# JLinkWiFi.net
KiCad netlist of a schematic drawn in EasyEDA Pro
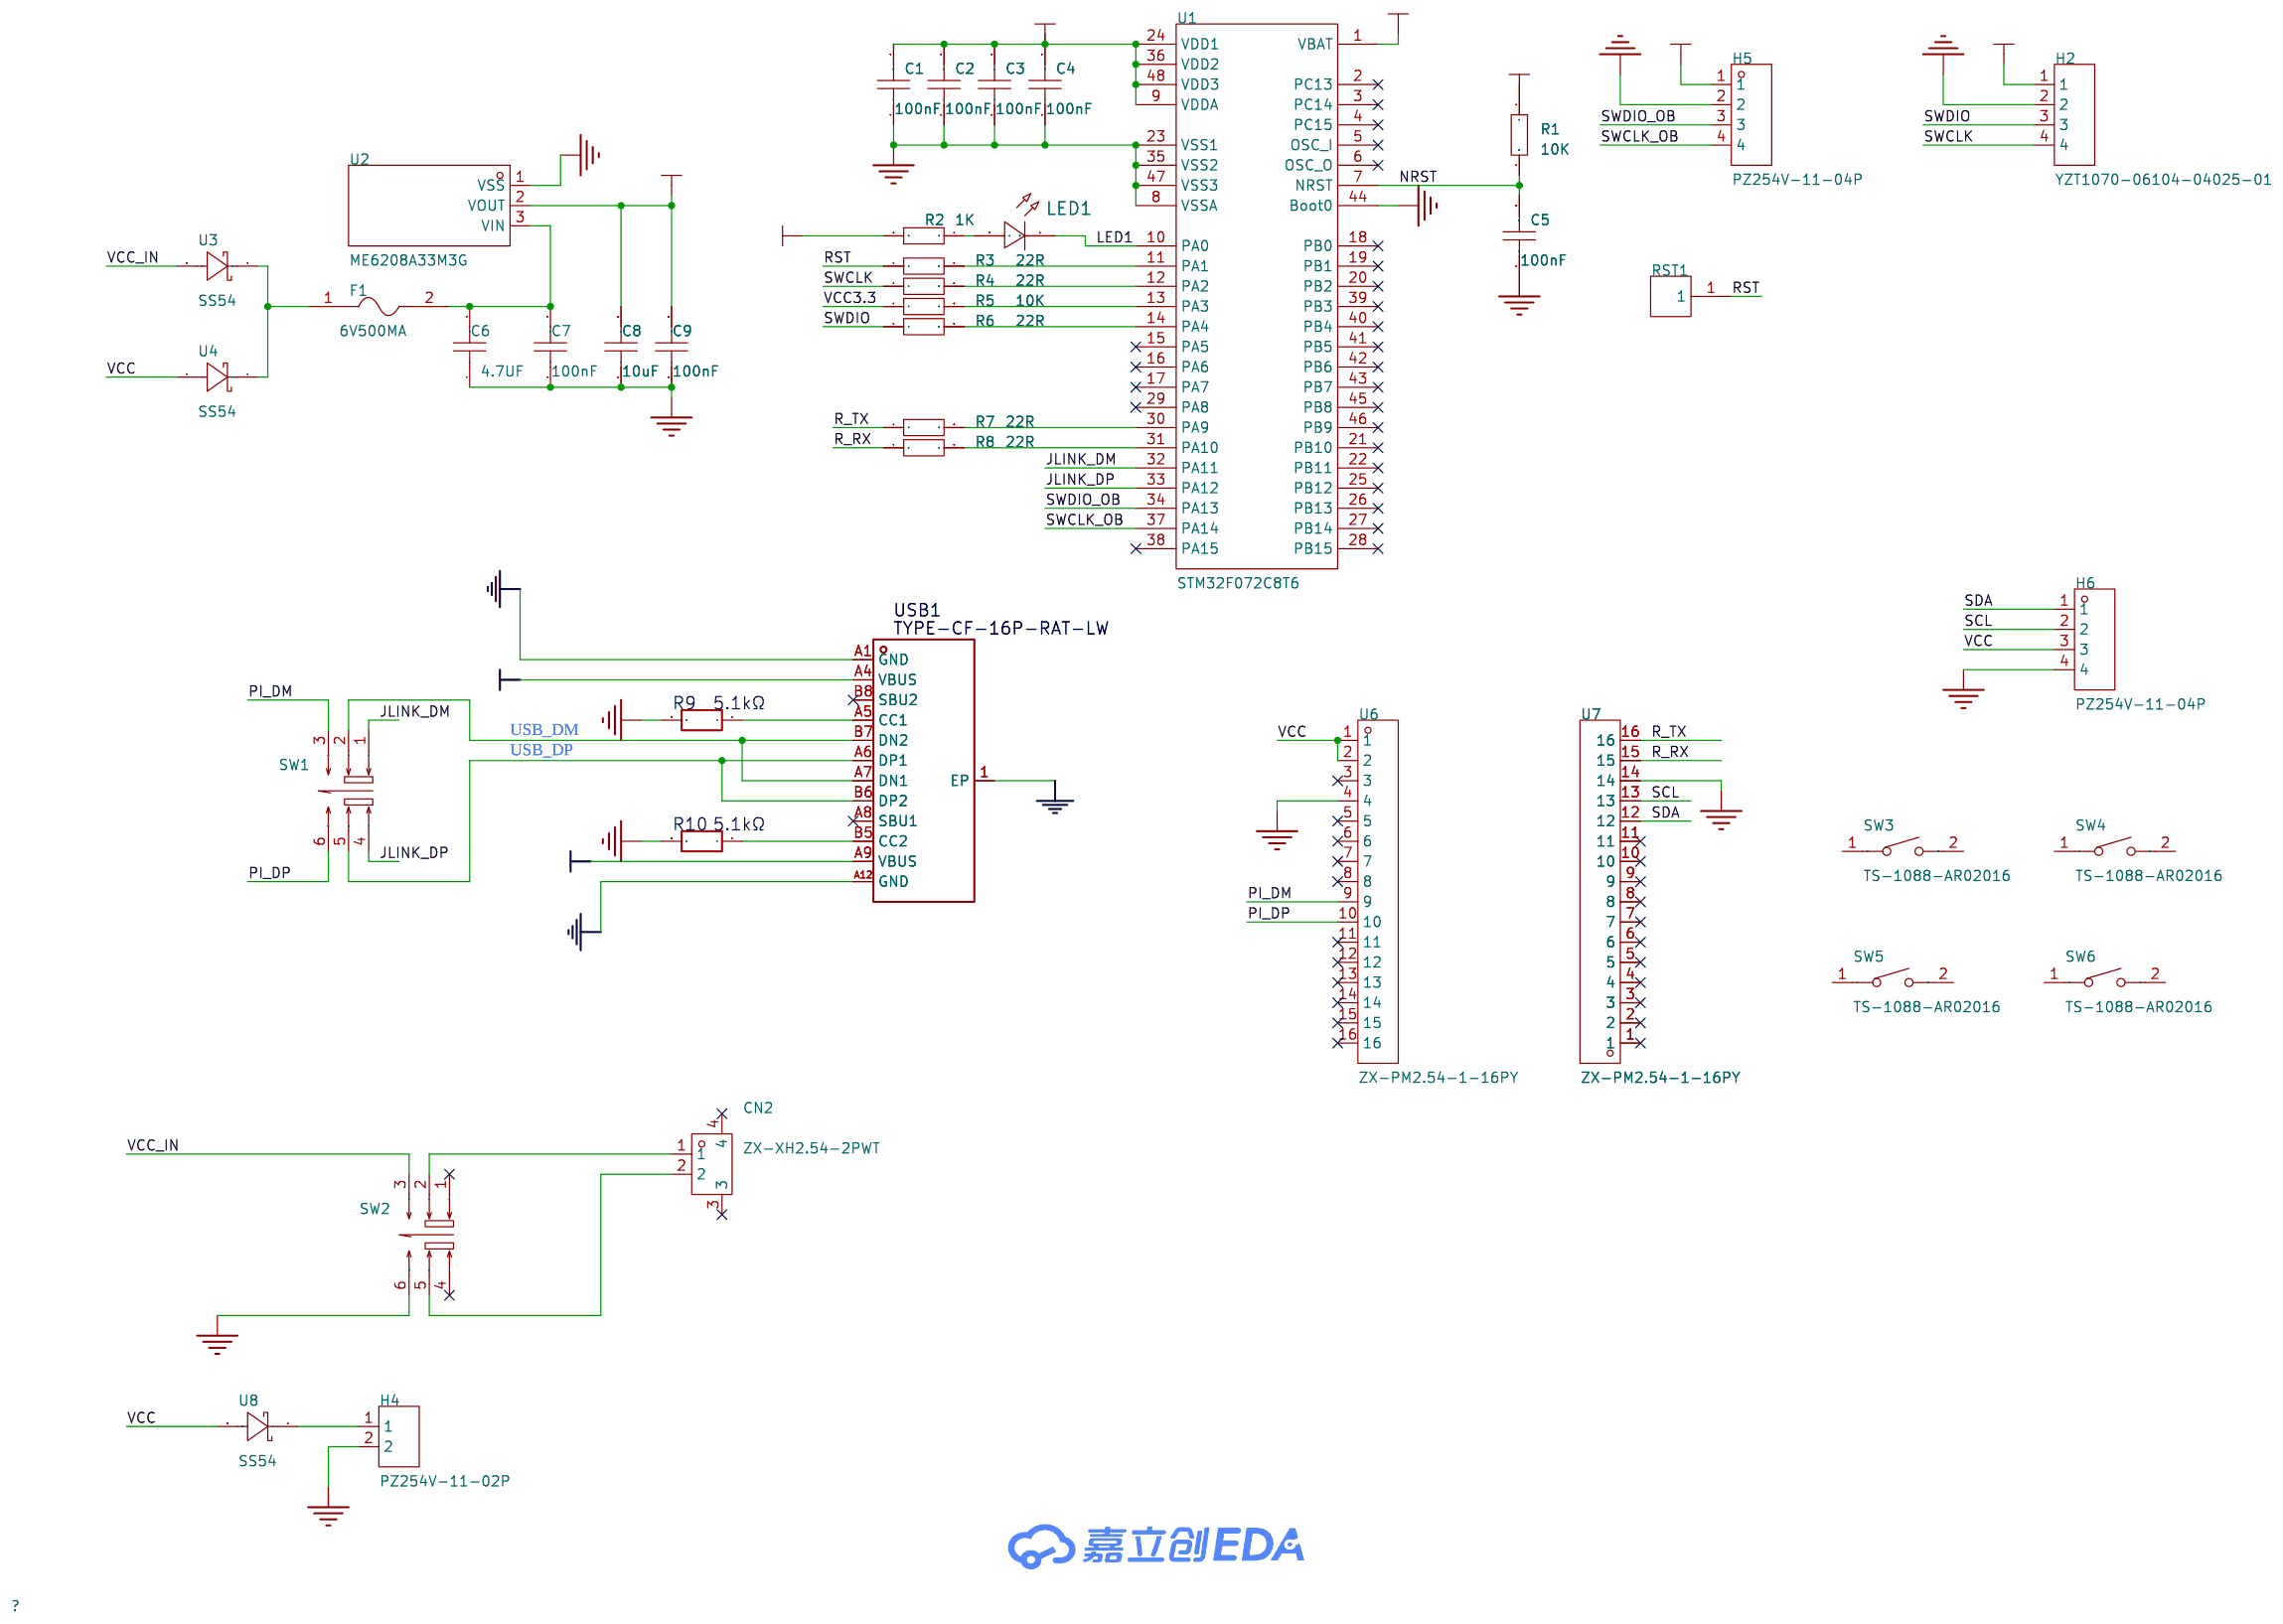
[diagram p0: schematic sheet]

(export (version "E")
  (design (tool "Eeschema 10.0.6"))
  (components
    (comp (ref "C1")
      (value "100nF")
      (footprint "easyedapro:C0603")
      (libsource (lib "easyedapro") (part "CapAcitance"))
    )
    (comp (ref "C2")
      (value "100nF")
      (footprint "easyedapro:C0603")
      (libsource (lib "easyedapro") (part "CapAcitance"))
    )
    (comp (ref "C3")
      (value "100nF")
      (footprint "easyedapro:C0603")
      (libsource (lib "easyedapro") (part "CapAcitance"))
    )
    (comp (ref "C4")
      (value "100nF")
      (footprint "easyedapro:C0603")
      (libsource (lib "easyedapro") (part "CapAcitance"))
    )
    (comp (ref "C5")
      (value "100nF")
      (footprint "easyedapro:C0603")
      (libsource (lib "easyedapro") (part "CapAcitance"))
    )
    (comp (ref "C6")
      (value "4.7UF")
      (footprint "easyedapro:C0603")
      (libsource (lib "easyedapro") (part "CapAcitance"))
    )
    (comp (ref "C7")
      (value "100nF")
      (footprint "easyedapro:C0603")
      (libsource (lib "easyedapro") (part "CapAcitance"))
    )
    (comp (ref "C8")
      (value "10uF")
      (footprint "easyedapro:C0603")
      (libsource (lib "easyedapro") (part "CapAcitance"))
    )
    (comp (ref "C9")
      (value "100nF")
      (footprint "easyedapro:C0603")
      (libsource (lib "easyedapro") (part "CapAcitance"))
    )
    (comp (ref "CN2")
      (value "ZX-XH2.54-2PWT")
      (footprint "easyedapro:CONN-SMD_2P-P2.54_MEGASTAR_ZX-XH2.54-2PWT")
      (fields (field (name "Manufacturer") "Megastar(兆星)"))
      (libsource (lib "easyedapro") (part "ZX-XH2.54-2PWT"))
    )
    (comp (ref "F1")
      (value "6V500MA")
      (footprint "easyedapro:F0805")
      (description "最大电压:24V;最大电流:100A;保持电流:100mA;跳闸电流:300mA;")
      (fields (field (name "Manufacturer") "台湾陆海"))
      (libsource (lib "easyedapro") (part "SMD0805-010-24V"))
    )
    (comp (ref "H2")
      (value "YZT1070-06104-04025-01")
      (footprint "easyedapro:HDR-TH_4P-P2.54-H-M-W6.0")
      (description "间距:2.54mm;总PIN位数:4P;")
      (fields (field (name "Manufacturer") "Xinyangze(鑫扬泽)"))
      (libsource (lib "easyedapro") (part "YZT1070-06104-04025-01"))
    )
    (comp (ref "H4")
      (value "PZ254V-11-02P")
      (footprint "easyedapro:HDR-TH_2P-P2.54-V-M")
      (fields (field (name "Manufacturer") "XFCN(兴飞)"))
      (libsource (lib "easyedapro") (part "PZ254V-11-02P"))
    )
    (comp (ref "H5")
      (value "PZ254V-11-04P")
      (footprint "easyedapro:HDR-TH_4P-P2.54-V-M")
      (fields (field (name "Manufacturer") "XFCN(兴飞)"))
      (libsource (lib "easyedapro") (part "PZ254V-11-04P_C2691448"))
    )
    (comp (ref "H6")
      (value "PZ254V-11-04P")
      (footprint "easyedapro:HDR-TH_4P-P2.54-V-M")
      (fields (field (name "Manufacturer") "XFCN(兴飞)"))
      (libsource (lib "easyedapro") (part "PZ254V-11-04P_C2691448"))
    )
    (comp (ref "LED1")
      (value "~")
      (footprint "easyedapro:LED_0603")
      (libsource (lib "easyedapro") (part "LED_R"))
    )
    (comp (ref "R1") (value "10K") (footprint "easyedapro:R0603") (libsource (lib "easyedapro") (part "电阻")))
    (comp (ref "R2") (value "1K") (footprint "easyedapro:R0603") (libsource (lib "easyedapro") (part "电阻")))
    (comp (ref "R3") (value "22R") (footprint "easyedapro:R0603") (libsource (lib "easyedapro") (part "电阻")))
    (comp (ref "R4") (value "22R") (footprint "easyedapro:R0603") (libsource (lib "easyedapro") (part "电阻")))
    (comp (ref "R5") (value "10K") (footprint "easyedapro:R0603") (libsource (lib "easyedapro") (part "电阻")))
    (comp (ref "R6") (value "22R") (footprint "easyedapro:R0603") (libsource (lib "easyedapro") (part "电阻")))
    (comp (ref "R7") (value "22R") (footprint "easyedapro:R0603") (libsource (lib "easyedapro") (part "电阻")))
    (comp (ref "R8") (value "22R") (footprint "easyedapro:R0603") (libsource (lib "easyedapro") (part "电阻")))
    (comp (ref "R9")
      (value "5.1kΩ")
      (footprint "easyedapro:R0603")
      (fields
        (field (name "Manufacturer Part") "MCT0603MG1002BP500")
        (field (name "Manufacturer") "VISHAY(威世)")
      )
      (libsource (lib "easyedapro") (part "10kΩ"))
    )
    (comp (ref "R10")
      (value "5.1kΩ")
      (footprint "easyedapro:R0603")
      (fields
        (field (name "Manufacturer Part") "MCT0603MG1002BP500")
        (field (name "Manufacturer") "VISHAY(威世)")
      )
      (libsource (lib "easyedapro") (part "10kΩ"))
    )
    (comp (ref "RST1")
      (value "~")
      (footprint "easyedapro:PAD_1.5*1.5MM")
      (libsource (lib "easyedapro") (part "测试点1.5x1.5mm"))
    )
    (comp (ref "SW1")
      (value "XKB5858-Z-TP-75")
      (footprint "easyedapro:SW-SMD_6P-L5.8-W5.8-P2.00-LS8.2-BL")
      (description "自锁/无锁:自锁;安装方式:立贴;触点电流:100mA;额定电压:30V;带灯:不带;作用力:1.6N;工作寿命:10万次;")
      (fields (field (name "Manufacturer") "XKB Connection(中国星坤)"))
      (libsource (lib "easyedapro") (part "XKB5858-Z-TP-75"))
    )
    (comp (ref "SW2")
      (value "XKB5858-Z-TP-75")
      (footprint "easyedapro:SW-SMD_6P-L5.8-W5.8-P2.00-LS8.2-BL")
      (description "自锁/无锁:自锁;安装方式:立贴;触点电流:100mA;额定电压:30V;带灯:不带;作用力:1.6N;工作寿命:10万次;")
      (fields (field (name "Manufacturer") "XKB Connection(中国星坤)"))
      (libsource (lib "easyedapro") (part "XKB5858-Z-TP-75"))
    )
    (comp (ref "SW3")
      (value "TS-1088-AR02016")
      (footprint "easyedapro:SW-SMD_L3.9-W3.0-P4.45")
      (fields (field (name "Manufacturer") "XUNPU(讯普)"))
      (libsource (lib "easyedapro") (part "TS-1088-AR02016"))
    )
    (comp (ref "SW4")
      (value "TS-1088-AR02016")
      (footprint "easyedapro:SW-SMD_L3.9-W3.0-P4.45")
      (fields (field (name "Manufacturer") "XUNPU(讯普)"))
      (libsource (lib "easyedapro") (part "TS-1088-AR02016"))
    )
    (comp (ref "SW5")
      (value "TS-1088-AR02016")
      (footprint "easyedapro:SW-SMD_L3.9-W3.0-P4.45")
      (fields (field (name "Manufacturer") "XUNPU(讯普)"))
      (libsource (lib "easyedapro") (part "TS-1088-AR02016"))
    )
    (comp (ref "SW6")
      (value "TS-1088-AR02016")
      (footprint "easyedapro:SW-SMD_L3.9-W3.0-P4.45")
      (fields (field (name "Manufacturer") "XUNPU(讯普)"))
      (libsource (lib "easyedapro") (part "TS-1088-AR02016"))
    )
    (comp (ref "U1")
      (value "STM32F072C8T6")
      (footprint "easyedapro:LQFP-48_L7.0-W7.0-P0.50-LS9.0-BL")
      (fields (field (name "Manufacturer") "ST(意法半导体)"))
      (libsource (lib "easyedapro") (part "STM32F072C8T6"))
    )
    (comp (ref "U2")
      (value "ME6208A33M3G")
      (footprint "easyedapro:SOT-23-3_L2.9-W1.3-P1.90-LS2.4-BR")
      (description "输出类型:固定;输出极性:正;最大输入电压:18V;输出电压:3.3V;输出电流:200mA;电源纹波抑制比(PSRR):-;")
      (fields (field (name "Manufacturer") "MICRONE(南京微盟)"))
      (libsource (lib "easyedapro") (part "ME6208A33M3G"))
    )
    (comp (ref "U3")
      (value "SS54")
      (footprint "easyedapro:SMB_L4.3-W3.6-LS5.4-RD")
      (description "二极管配置:独立式;正向压降(Vf):550mV@5A;直流反向耐压(Vr):40V;整流电流:5A;")
      (fields (field (name "Manufacturer") "HXY MOSFET(华轩阳电子)"))
      (libsource (lib "easyedapro") (part "SS54_C5200096"))
    )
    (comp (ref "U4")
      (value "SS54")
      (footprint "easyedapro:SMB_L4.3-W3.6-LS5.4-RD")
      (description "二极管配置:独立式;正向压降(Vf):550mV@5A;直流反向耐压(Vr):40V;整流电流:5A;")
      (fields (field (name "Manufacturer") "HXY MOSFET(华轩阳电子)"))
      (libsource (lib "easyedapro") (part "SS54_C5200096"))
    )
    (comp (ref "U6")
      (value "ZX-PM2.54-1-16PY")
      (footprint "easyedapro:HDR-TH_16P-P2.54-V-F-1")
      (fields (field (name "Manufacturer") "Megastar(兆星)"))
      (libsource (lib "easyedapro") (part "ZX-PM2.54-1-16PY"))
    )
    (comp (ref "U7")
      (value "ZX-PM2.54-1-16PY")
      (footprint "easyedapro:HDR-TH_16P-P2.54-V-F-1")
      (fields (field (name "Manufacturer") "Megastar(兆星)"))
      (libsource (lib "easyedapro") (part "ZX-PM2.54-1-16PY"))
    )
    (comp (ref "U8")
      (value "SS54")
      (footprint "easyedapro:SMB_L4.3-W3.6-LS5.4-RD")
      (description "二极管配置:独立式;正向压降(Vf):550mV@5A;直流反向耐压(Vr):40V;整流电流:5A;")
      (fields (field (name "Manufacturer") "HXY MOSFET(华轩阳电子)"))
      (libsource (lib "easyedapro") (part "SS54_C5200096"))
    )
    (comp (ref "USB1")
      (value "TYPE-CF-16P-RAT-LW")
      (footprint "easyedapro:TYPE-C-SMD_TYPE-CF-16P-RAT-LW")
      (libsource (lib "easyedapro") (part "TYPE-CF-16P-RAT-LW"))
    )
  )
  (nets
    (net (code "1") (name "/JLINK_DM") (class "Default")
      (node (ref "SW1") (pin "1") (pinfunction "1_1") (pintype "unspecified"))
      (node (ref "U1") (pin "32") (pinfunction "PA11_32") (pintype "input"))
    )
    (net (code "2") (name "/JLINK_DP") (class "Default")
      (node (ref "SW1") (pin "4") (pinfunction "4_4") (pintype "unspecified"))
      (node (ref "U1") (pin "33") (pinfunction "PA12_33") (pintype "input"))
    )
    (net (code "3") (name "/LED1") (class "Default")
      (node (ref "LED1") (pin "1") (pinfunction "C_1") (pintype "input"))
      (node (ref "U1") (pin "10") (pinfunction "PA0_10") (pintype "input"))
    )
    (net (code "4") (name "/NRST") (class "Default")
      (node (ref "C5") (pin "2") (pinfunction "2_2") (pintype "input"))
      (node (ref "R1") (pin "2") (pinfunction "2_2") (pintype "input"))
      (node (ref "U1") (pin "7") (pinfunction "NRST_7") (pintype "input"))
    )
    (net (code "5") (name "/PI_DM") (class "Default")
      (node (ref "SW1") (pin "3") (pinfunction "3_3") (pintype "unspecified"))
      (node (ref "U6") (pin "9") (pinfunction "9_9") (pintype "unspecified"))
    )
    (net (code "6") (name "/PI_DP") (class "Default")
      (node (ref "SW1") (pin "6") (pinfunction "6_6") (pintype "unspecified"))
      (node (ref "U6") (pin "10") (pinfunction "10_10") (pintype "unspecified"))
    )
    (net (code "7") (name "/RST") (class "Default")
      (node (ref "R3") (pin "1") (pinfunction "1_1") (pintype "input"))
      (node (ref "RST1") (pin "1") (pinfunction "1_1") (pintype "input"))
    )
    (net (code "8") (name "/R_RX") (class "Default")
      (node (ref "R8") (pin "1") (pinfunction "1_1") (pintype "input"))
      (node (ref "U7") (pin "15") (pinfunction "15_15") (pintype "unspecified"))
    )
    (net (code "9") (name "/R_TX") (class "Default")
      (node (ref "R7") (pin "1") (pinfunction "1_1") (pintype "input"))
      (node (ref "U7") (pin "16") (pinfunction "16_16") (pintype "unspecified"))
    )
    (net (code "10") (name "/SCL") (class "Default")
      (node (ref "H6") (pin "2") (pinfunction "2_2") (pintype "unspecified"))
      (node (ref "U7") (pin "13") (pinfunction "13_13") (pintype "unspecified"))
    )
    (net (code "11") (name "/SDA") (class "Default")
      (node (ref "H6") (pin "1") (pinfunction "1_1") (pintype "unspecified"))
      (node (ref "U7") (pin "12") (pinfunction "12_12") (pintype "unspecified"))
    )
    (net (code "12") (name "/SWCLK") (class "Default")
      (node (ref "H2") (pin "4") (pinfunction "4_4") (pintype "unspecified"))
      (node (ref "R4") (pin "1") (pinfunction "1_1") (pintype "input"))
    )
    (net (code "13") (name "/SWCLK_OB") (class "Default")
      (node (ref "H5") (pin "4") (pinfunction "4_4") (pintype "unspecified"))
      (node (ref "U1") (pin "37") (pinfunction "PA14_37") (pintype "input"))
    )
    (net (code "14") (name "/SWDIO") (class "Default")
      (node (ref "H2") (pin "3") (pinfunction "3_3") (pintype "unspecified"))
      (node (ref "R6") (pin "1") (pinfunction "1_1") (pintype "input"))
    )
    (net (code "15") (name "/SWDIO_OB") (class "Default")
      (node (ref "H5") (pin "3") (pinfunction "3_3") (pintype "unspecified"))
      (node (ref "U1") (pin "34") (pinfunction "PA13_34") (pintype "input"))
    )
    (net (code "16") (name "/USB_DM") (class "Default")
      (node (ref "SW1") (pin "2") (pinfunction "2_2") (pintype "unspecified"))
      (node (ref "USB1") (pin "A7") (pinfunction "DN1_A7") (pintype "unspecified"))
      (node (ref "USB1") (pin "B7") (pinfunction "DN2_B7") (pintype "unspecified"))
    )
    (net (code "17") (name "/USB_DP") (class "Default")
      (node (ref "SW1") (pin "5") (pinfunction "5_5") (pintype "unspecified"))
      (node (ref "USB1") (pin "A6") (pinfunction "DP1_A6") (pintype "unspecified"))
      (node (ref "USB1") (pin "B6") (pinfunction "DP2_B6") (pintype "unspecified"))
    )
    (net (code "18") (name "/VCC_IN") (class "Default")
      (node (ref "SW2") (pin "3") (pinfunction "3_3") (pintype "unspecified"))
      (node (ref "U3") (pin "2") (pinfunction "2_2") (pintype "unspecified"))
    )
    (net (code "19") (name "GND") (class "Default")
      (node (ref "C1") (pin "1") (pinfunction "1_1") (pintype "input"))
      (node (ref "C2") (pin "1") (pinfunction "1_1") (pintype "input"))
      (node (ref "C3") (pin "1") (pinfunction "1_1") (pintype "input"))
      (node (ref "C4") (pin "1") (pinfunction "1_1") (pintype "input"))
      (node (ref "C5") (pin "1") (pinfunction "1_1") (pintype "input"))
      (node (ref "C6") (pin "1") (pinfunction "1_1") (pintype "input"))
      (node (ref "C7") (pin "1") (pinfunction "1_1") (pintype "input"))
      (node (ref "C8") (pin "1") (pinfunction "1_1") (pintype "input"))
      (node (ref "C9") (pin "1") (pinfunction "1_1") (pintype "input"))
      (node (ref "H2") (pin "2") (pinfunction "2_2") (pintype "unspecified"))
      (node (ref "H4") (pin "2") (pinfunction "2_2") (pintype "unspecified"))
      (node (ref "H5") (pin "2") (pinfunction "2_2") (pintype "unspecified"))
      (node (ref "H6") (pin "4") (pinfunction "4_4") (pintype "unspecified"))
      (node (ref "R10") (pin "2") (pinfunction "2_2") (pintype "unspecified"))
      (node (ref "R9") (pin "2") (pinfunction "2_2") (pintype "unspecified"))
      (node (ref "SW2") (pin "6") (pinfunction "6_6") (pintype "unspecified"))
      (node (ref "U1") (pin "23") (pinfunction "VSS1_23") (pintype "input"))
      (node (ref "U1") (pin "35") (pinfunction "VSS2_35") (pintype "input"))
      (node (ref "U1") (pin "44") (pinfunction "Boot0_44") (pintype "input"))
      (node (ref "U1") (pin "47") (pinfunction "VSS3_47") (pintype "input"))
      (node (ref "U1") (pin "8") (pinfunction "VSSA_8") (pintype "input"))
      (node (ref "U2") (pin "1") (pinfunction "VSS_1") (pintype "input"))
      (node (ref "U6") (pin "4") (pinfunction "4_4") (pintype "unspecified"))
      (node (ref "U7") (pin "14") (pinfunction "14_14") (pintype "unspecified"))
      (node (ref "USB1") (pin "1") (pinfunction "EP_1") (pintype "unspecified"))
      (node (ref "USB1") (pin "A1") (pinfunction "GND_A1") (pintype "unspecified"))
      (node (ref "USB1") (pin "A12") (pinfunction "GND_A12") (pintype "unspecified"))
    )
    (net (code "20") (name "Net-(CN2-Pad1)") (class "Default")
      (node (ref "CN2") (pin "1") (pinfunction "1_1") (pintype "unspecified"))
      (node (ref "SW2") (pin "2") (pinfunction "2_2") (pintype "unspecified"))
    )
    (net (code "21") (name "Net-(CN2-Pad2)") (class "Default")
      (node (ref "CN2") (pin "2") (pinfunction "2_2") (pintype "unspecified"))
      (node (ref "SW2") (pin "5") (pinfunction "5_5") (pintype "unspecified"))
    )
    (net (code "22") (name "Net-(F1-Pad1)") (class "Default")
      (node (ref "F1") (pin "1") (pinfunction "1_1") (pintype "input"))
      (node (ref "U3") (pin "1") (pinfunction "1_1") (pintype "unspecified"))
      (node (ref "U4") (pin "1") (pinfunction "1_1") (pintype "unspecified"))
    )
    (net (code "23") (name "Net-(H4-Pad1)") (class "Default")
      (node (ref "H4") (pin "1") (pinfunction "1_1") (pintype "unspecified"))
      (node (ref "U8") (pin "1") (pinfunction "1_1") (pintype "unspecified"))
    )
    (net (code "24") (name "Net-(LED1-A)") (class "Default")
      (node (ref "LED1") (pin "2") (pinfunction "A_2") (pintype "input"))
      (node (ref "R2") (pin "1") (pinfunction "1_1") (pintype "input"))
    )
    (net (code "25") (name "Net-(U1-PA1)") (class "Default")
      (node (ref "R3") (pin "2") (pinfunction "2_2") (pintype "input"))
      (node (ref "U1") (pin "11") (pinfunction "PA1_11") (pintype "input"))
    )
    (net (code "26") (name "Net-(U1-PA2)") (class "Default")
      (node (ref "R4") (pin "2") (pinfunction "2_2") (pintype "input"))
      (node (ref "U1") (pin "12") (pinfunction "PA2_12") (pintype "input"))
    )
    (net (code "27") (name "Net-(U1-PA3)") (class "Default")
      (node (ref "R5") (pin "2") (pinfunction "2_2") (pintype "input"))
      (node (ref "U1") (pin "13") (pinfunction "PA3_13") (pintype "input"))
    )
    (net (code "28") (name "Net-(U1-PA4)") (class "Default")
      (node (ref "R6") (pin "2") (pinfunction "2_2") (pintype "input"))
      (node (ref "U1") (pin "14") (pinfunction "PA4_14") (pintype "input"))
    )
    (net (code "29") (name "Net-(U1-PA9)") (class "Default")
      (node (ref "R7") (pin "2") (pinfunction "2_2") (pintype "input"))
      (node (ref "U1") (pin "30") (pinfunction "PA9_30") (pintype "input"))
    )
    (net (code "30") (name "Net-(U1-PA10)") (class "Default")
      (node (ref "R8") (pin "2") (pinfunction "2_2") (pintype "input"))
      (node (ref "U1") (pin "31") (pinfunction "PA10_31") (pintype "input"))
    )
    (net (code "31") (name "Net-(U2-VIN)") (class "Default")
      (node (ref "C6") (pin "2") (pinfunction "2_2") (pintype "input"))
      (node (ref "C7") (pin "2") (pinfunction "2_2") (pintype "input"))
      (node (ref "F1") (pin "2") (pinfunction "2_2") (pintype "input"))
      (node (ref "U2") (pin "3") (pinfunction "VIN_3") (pintype "input"))
    )
    (net (code "32") (name "Net-(USB1-CC1)") (class "Default")
      (node (ref "R9") (pin "1") (pinfunction "1_1") (pintype "unspecified"))
      (node (ref "USB1") (pin "A5") (pinfunction "CC1_A5") (pintype "unspecified"))
    )
    (net (code "33") (name "Net-(USB1-CC2)") (class "Default")
      (node (ref "R10") (pin "1") (pinfunction "1_1") (pintype "unspecified"))
      (node (ref "USB1") (pin "B5") (pinfunction "CC2_B5") (pintype "unspecified"))
    )
    (net (code "34") (name "VCC") (class "Default")
      (node (ref "H6") (pin "3") (pinfunction "3_3") (pintype "unspecified"))
      (node (ref "U4") (pin "2") (pinfunction "2_2") (pintype "unspecified"))
      (node (ref "U6") (pin "1") (pinfunction "1_1") (pintype "unspecified"))
      (node (ref "U6") (pin "2") (pinfunction "2_2") (pintype "unspecified"))
      (node (ref "U8") (pin "2") (pinfunction "2_2") (pintype "unspecified"))
      (node (ref "USB1") (pin "A4") (pinfunction "VBUS_A4") (pintype "unspecified"))
      (node (ref "USB1") (pin "A9") (pinfunction "VBUS_A9") (pintype "unspecified"))
    )
    (net (code "35") (name "VCC3.3") (class "Default")
      (node (ref "C1") (pin "2") (pinfunction "2_2") (pintype "input"))
      (node (ref "C2") (pin "2") (pinfunction "2_2") (pintype "input"))
      (node (ref "C3") (pin "2") (pinfunction "2_2") (pintype "input"))
      (node (ref "C4") (pin "2") (pinfunction "2_2") (pintype "input"))
      (node (ref "C8") (pin "2") (pinfunction "2_2") (pintype "input"))
      (node (ref "C9") (pin "2") (pinfunction "2_2") (pintype "input"))
      (node (ref "H2") (pin "1") (pinfunction "1_1") (pintype "unspecified"))
      (node (ref "H5") (pin "1") (pinfunction "1_1") (pintype "unspecified"))
      (node (ref "R1") (pin "1") (pinfunction "1_1") (pintype "input"))
      (node (ref "R2") (pin "2") (pinfunction "2_2") (pintype "input"))
      (node (ref "R5") (pin "1") (pinfunction "1_1") (pintype "input"))
      (node (ref "U1") (pin "1") (pinfunction "VBAT_1") (pintype "input"))
      (node (ref "U1") (pin "24") (pinfunction "VDD1_24") (pintype "input"))
      (node (ref "U1") (pin "36") (pinfunction "VDD2_36") (pintype "input"))
      (node (ref "U1") (pin "48") (pinfunction "VDD3_48") (pintype "input"))
      (node (ref "U1") (pin "9") (pinfunction "VDDA_9") (pintype "input"))
      (node (ref "U2") (pin "2") (pinfunction "VOUT_2") (pintype "input"))
    )
    (net (code "36") (name "unconnected-(CN2-Pad3)") (class "Default")
      (node (ref "CN2") (pin "3") (pinfunction "3_3") (pintype "unspecified+no_connect"))
    )
    (net (code "37") (name "unconnected-(CN2-Pad4)") (class "Default")
      (node (ref "CN2") (pin "4") (pinfunction "4_4") (pintype "unspecified+no_connect"))
    )
    (net (code "38") (name "unconnected-(SW2-Pad1)") (class "Default")
      (node (ref "SW2") (pin "1") (pinfunction "1_1") (pintype "unspecified+no_connect"))
    )
    (net (code "39") (name "unconnected-(SW2-Pad4)") (class "Default")
      (node (ref "SW2") (pin "4") (pinfunction "4_4") (pintype "unspecified+no_connect"))
    )
    (net (code "40") (name "unconnected-(SW3-Pad1)") (class "Default")
      (node (ref "SW3") (pin "1") (pinfunction "1_1") (pintype "unspecified"))
    )
    (net (code "41") (name "unconnected-(SW3-Pad2)") (class "Default")
      (node (ref "SW3") (pin "2") (pinfunction "2_2") (pintype "unspecified"))
    )
    (net (code "42") (name "unconnected-(SW4-Pad1)") (class "Default")
      (node (ref "SW4") (pin "1") (pinfunction "1_1") (pintype "unspecified"))
    )
    (net (code "43") (name "unconnected-(SW4-Pad2)") (class "Default")
      (node (ref "SW4") (pin "2") (pinfunction "2_2") (pintype "unspecified"))
    )
    (net (code "44") (name "unconnected-(SW5-Pad1)") (class "Default")
      (node (ref "SW5") (pin "1") (pinfunction "1_1") (pintype "unspecified"))
    )
    (net (code "45") (name "unconnected-(SW5-Pad2)") (class "Default")
      (node (ref "SW5") (pin "2") (pinfunction "2_2") (pintype "unspecified"))
    )
    (net (code "46") (name "unconnected-(SW6-Pad1)") (class "Default")
      (node (ref "SW6") (pin "1") (pinfunction "1_1") (pintype "unspecified"))
    )
    (net (code "47") (name "unconnected-(SW6-Pad2)") (class "Default")
      (node (ref "SW6") (pin "2") (pinfunction "2_2") (pintype "unspecified"))
    )
    (net (code "48") (name "unconnected-(U1-OSC_I-Pad5)") (class "Default")
      (node (ref "U1") (pin "5") (pinfunction "OSC_I_5") (pintype "input+no_connect"))
    )
    (net (code "49") (name "unconnected-(U1-OSC_O-Pad6)") (class "Default")
      (node (ref "U1") (pin "6") (pinfunction "OSC_O_6") (pintype "input+no_connect"))
    )
    (net (code "50") (name "unconnected-(U1-PA5-Pad15)") (class "Default")
      (node (ref "U1") (pin "15") (pinfunction "PA5_15") (pintype "input+no_connect"))
    )
    (net (code "51") (name "unconnected-(U1-PA6-Pad16)") (class "Default")
      (node (ref "U1") (pin "16") (pinfunction "PA6_16") (pintype "input+no_connect"))
    )
    (net (code "52") (name "unconnected-(U1-PA7-Pad17)") (class "Default")
      (node (ref "U1") (pin "17") (pinfunction "PA7_17") (pintype "input+no_connect"))
    )
    (net (code "53") (name "unconnected-(U1-PA8-Pad29)") (class "Default")
      (node (ref "U1") (pin "29") (pinfunction "PA8_29") (pintype "input+no_connect"))
    )
    (net (code "54") (name "unconnected-(U1-PA15-Pad38)") (class "Default")
      (node (ref "U1") (pin "38") (pinfunction "PA15_38") (pintype "input+no_connect"))
    )
    (net (code "55") (name "unconnected-(U1-PB0-Pad18)") (class "Default")
      (node (ref "U1") (pin "18") (pinfunction "PB0_18") (pintype "input+no_connect"))
    )
    (net (code "56") (name "unconnected-(U1-PB1-Pad19)") (class "Default")
      (node (ref "U1") (pin "19") (pinfunction "PB1_19") (pintype "input+no_connect"))
    )
    (net (code "57") (name "unconnected-(U1-PB2-Pad20)") (class "Default")
      (node (ref "U1") (pin "20") (pinfunction "PB2_20") (pintype "input+no_connect"))
    )
    (net (code "58") (name "unconnected-(U1-PB3-Pad39)") (class "Default")
      (node (ref "U1") (pin "39") (pinfunction "PB3_39") (pintype "input+no_connect"))
    )
    (net (code "59") (name "unconnected-(U1-PB4-Pad40)") (class "Default")
      (node (ref "U1") (pin "40") (pinfunction "PB4_40") (pintype "input+no_connect"))
    )
    (net (code "60") (name "unconnected-(U1-PB5-Pad41)") (class "Default")
      (node (ref "U1") (pin "41") (pinfunction "PB5_41") (pintype "input+no_connect"))
    )
    (net (code "61") (name "unconnected-(U1-PB6-Pad42)") (class "Default")
      (node (ref "U1") (pin "42") (pinfunction "PB6_42") (pintype "input+no_connect"))
    )
    (net (code "62") (name "unconnected-(U1-PB7-Pad43)") (class "Default")
      (node (ref "U1") (pin "43") (pinfunction "PB7_43") (pintype "input+no_connect"))
    )
    (net (code "63") (name "unconnected-(U1-PB8-Pad45)") (class "Default")
      (node (ref "U1") (pin "45") (pinfunction "PB8_45") (pintype "input+no_connect"))
    )
    (net (code "64") (name "unconnected-(U1-PB9-Pad46)") (class "Default")
      (node (ref "U1") (pin "46") (pinfunction "PB9_46") (pintype "input+no_connect"))
    )
    (net (code "65") (name "unconnected-(U1-PB10-Pad21)") (class "Default")
      (node (ref "U1") (pin "21") (pinfunction "PB10_21") (pintype "input+no_connect"))
    )
    (net (code "66") (name "unconnected-(U1-PB11-Pad22)") (class "Default")
      (node (ref "U1") (pin "22") (pinfunction "PB11_22") (pintype "input+no_connect"))
    )
    (net (code "67") (name "unconnected-(U1-PB12-Pad25)") (class "Default")
      (node (ref "U1") (pin "25") (pinfunction "PB12_25") (pintype "input+no_connect"))
    )
    (net (code "68") (name "unconnected-(U1-PB13-Pad26)") (class "Default")
      (node (ref "U1") (pin "26") (pinfunction "PB13_26") (pintype "input+no_connect"))
    )
    (net (code "69") (name "unconnected-(U1-PB14-Pad27)") (class "Default")
      (node (ref "U1") (pin "27") (pinfunction "PB14_27") (pintype "input+no_connect"))
    )
    (net (code "70") (name "unconnected-(U1-PB15-Pad28)") (class "Default")
      (node (ref "U1") (pin "28") (pinfunction "PB15_28") (pintype "input+no_connect"))
    )
    (net (code "71") (name "unconnected-(U1-PC13-Pad2)") (class "Default")
      (node (ref "U1") (pin "2") (pinfunction "PC13_2") (pintype "input+no_connect"))
    )
    (net (code "72") (name "unconnected-(U1-PC14-Pad3)") (class "Default")
      (node (ref "U1") (pin "3") (pinfunction "PC14_3") (pintype "input+no_connect"))
    )
    (net (code "73") (name "unconnected-(U1-PC15-Pad4)") (class "Default")
      (node (ref "U1") (pin "4") (pinfunction "PC15_4") (pintype "input+no_connect"))
    )
    (net (code "74") (name "unconnected-(U6-Pad3)") (class "Default")
      (node (ref "U6") (pin "3") (pinfunction "3_3") (pintype "unspecified+no_connect"))
    )
    (net (code "75") (name "unconnected-(U6-Pad5)") (class "Default")
      (node (ref "U6") (pin "5") (pinfunction "5_5") (pintype "unspecified+no_connect"))
    )
    (net (code "76") (name "unconnected-(U6-Pad6)") (class "Default")
      (node (ref "U6") (pin "6") (pinfunction "6_6") (pintype "unspecified+no_connect"))
    )
    (net (code "77") (name "unconnected-(U6-Pad7)") (class "Default")
      (node (ref "U6") (pin "7") (pinfunction "7_7") (pintype "unspecified+no_connect"))
    )
    (net (code "78") (name "unconnected-(U6-Pad8)") (class "Default")
      (node (ref "U6") (pin "8") (pinfunction "8_8") (pintype "unspecified+no_connect"))
    )
    (net (code "79") (name "unconnected-(U6-Pad11)") (class "Default")
      (node (ref "U6") (pin "11") (pinfunction "11_11") (pintype "unspecified+no_connect"))
    )
    (net (code "80") (name "unconnected-(U6-Pad12)") (class "Default")
      (node (ref "U6") (pin "12") (pinfunction "12_12") (pintype "unspecified+no_connect"))
    )
    (net (code "81") (name "unconnected-(U6-Pad13)") (class "Default")
      (node (ref "U6") (pin "13") (pinfunction "13_13") (pintype "unspecified+no_connect"))
    )
    (net (code "82") (name "unconnected-(U6-Pad14)") (class "Default")
      (node (ref "U6") (pin "14") (pinfunction "14_14") (pintype "unspecified+no_connect"))
    )
    (net (code "83") (name "unconnected-(U6-Pad15)") (class "Default")
      (node (ref "U6") (pin "15") (pinfunction "15_15") (pintype "unspecified+no_connect"))
    )
    (net (code "84") (name "unconnected-(U6-Pad16)") (class "Default")
      (node (ref "U6") (pin "16") (pinfunction "16_16") (pintype "unspecified+no_connect"))
    )
    (net (code "85") (name "unconnected-(U7-Pad1)") (class "Default")
      (node (ref "U7") (pin "1") (pinfunction "1_1") (pintype "unspecified+no_connect"))
    )
    (net (code "86") (name "unconnected-(U7-Pad2)") (class "Default")
      (node (ref "U7") (pin "2") (pinfunction "2_2") (pintype "unspecified+no_connect"))
    )
    (net (code "87") (name "unconnected-(U7-Pad3)") (class "Default")
      (node (ref "U7") (pin "3") (pinfunction "3_3") (pintype "unspecified+no_connect"))
    )
    (net (code "88") (name "unconnected-(U7-Pad4)") (class "Default")
      (node (ref "U7") (pin "4") (pinfunction "4_4") (pintype "unspecified+no_connect"))
    )
    (net (code "89") (name "unconnected-(U7-Pad5)") (class "Default")
      (node (ref "U7") (pin "5") (pinfunction "5_5") (pintype "unspecified+no_connect"))
    )
    (net (code "90") (name "unconnected-(U7-Pad6)") (class "Default")
      (node (ref "U7") (pin "6") (pinfunction "6_6") (pintype "unspecified+no_connect"))
    )
    (net (code "91") (name "unconnected-(U7-Pad7)") (class "Default")
      (node (ref "U7") (pin "7") (pinfunction "7_7") (pintype "unspecified+no_connect"))
    )
    (net (code "92") (name "unconnected-(U7-Pad8)") (class "Default")
      (node (ref "U7") (pin "8") (pinfunction "8_8") (pintype "unspecified+no_connect"))
    )
    (net (code "93") (name "unconnected-(U7-Pad9)") (class "Default")
      (node (ref "U7") (pin "9") (pinfunction "9_9") (pintype "unspecified+no_connect"))
    )
    (net (code "94") (name "unconnected-(U7-Pad10)") (class "Default")
      (node (ref "U7") (pin "10") (pinfunction "10_10") (pintype "unspecified+no_connect"))
    )
    (net (code "95") (name "unconnected-(U7-Pad11)") (class "Default")
      (node (ref "U7") (pin "11") (pinfunction "11_11") (pintype "unspecified+no_connect"))
    )
    (net (code "96") (name "unconnected-(USB1-SBU1-PadA8)") (class "Default")
      (node (ref "USB1") (pin "A8") (pinfunction "SBU1_A8") (pintype "unspecified+no_connect"))
    )
    (net (code "97") (name "unconnected-(USB1-SBU2-PadB8)") (class "Default")
      (node (ref "USB1") (pin "B8") (pinfunction "SBU2_B8") (pintype "unspecified+no_connect"))
    )
  )
)
